# Controller.net
KiCad netlist of a schematic drawn in EAGLE
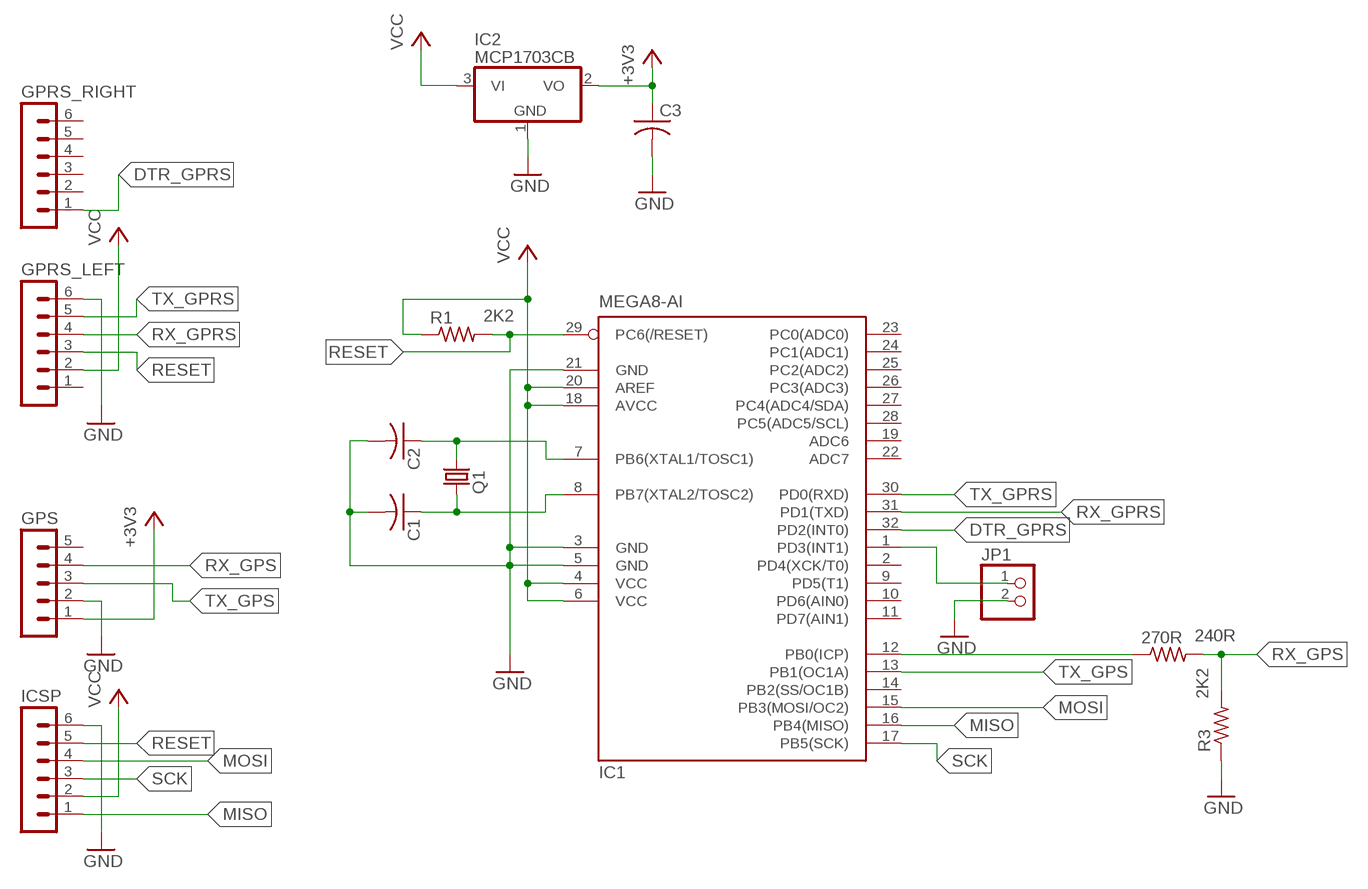
[diagram p0: schematic, sheet 1]

(export (version "E")
  (design (tool "Eeschema 10.0.6"))
  (components
    (comp (ref "270R")
      (value "240R")
      (footprint "eagle-import:M0805")
      (libsource (lib "eagle-import") (part "R-US_M0805"))
    )
    (comp (ref "C1")
      (value "C-US025-024X044")
      (footprint "eagle-import:C025-024X044")
      (libsource (lib "eagle-import") (part "C-US025-024X044"))
    )
    (comp (ref "C2")
      (value "C-US025-024X044")
      (footprint "eagle-import:C025-024X044")
      (libsource (lib "eagle-import") (part "C-US025-024X044"))
    )
    (comp (ref "C3")
      (value "C-US025-024X044")
      (footprint "eagle-import:C025-024X044")
      (libsource (lib "eagle-import") (part "C-US025-024X044"))
    )
    (comp (ref "GPRS_LEFT")
      (value "MA06-1")
      (footprint "eagle-import:MA06-1")
      (libsource (lib "eagle-import") (part "MA06-1"))
    )
    (comp (ref "GPRS_RIGHT")
      (value "MA06-1")
      (footprint "eagle-import:MA06-1")
      (libsource (lib "eagle-import") (part "MA06-1"))
    )
    (comp (ref "GPS")
      (value "MA05-1")
      (footprint "eagle-import:MA05-1")
      (libsource (lib "eagle-import") (part "MA05-1"))
    )
    (comp (ref "IC1")
      (value "MEGA8-AI")
      (footprint "eagle-import:TQFP32-08")
      (fields (field (name "MPN") "ATMEGA8-16AU"))
      (libsource (lib "eagle-import") (part "MEGA8-AI"))
    )
    (comp (ref "IC2")
      (value "MCP1703CB")
      (footprint "eagle-import:SOT23")
      (libsource (lib "eagle-import") (part "MCP1703CB"))
    )
    (comp (ref "ICSP")
      (value "MA06-1")
      (footprint "eagle-import:MA06-1")
      (libsource (lib "eagle-import") (part "MA06-1"))
    )
    (comp (ref "JP1")
      (value "PINHD-1X2")
      (footprint "eagle-import:1X02")
      (libsource (lib "eagle-import") (part "PINHD-1X2"))
    )
    (comp (ref "Q1")
      (value "CRYSTALHC49U-V")
      (footprint "eagle-import:HC49U-V")
      (libsource (lib "eagle-import") (part "CRYSTALHC49U-V"))
    )
    (comp (ref "R1")
      (value "2K2")
      (footprint "eagle-import:M0805")
      (libsource (lib "eagle-import") (part "R-US_M0805"))
    )
    (comp (ref "R3")
      (value "2K2")
      (footprint "eagle-import:M0805")
      (libsource (lib "eagle-import") (part "R-US_M0805"))
    )
  )
  (nets
    (net (code "1") (name "+3V3") (class "Default")
      (node (ref "C3") (pin "1") (pinfunction "1_1") (pintype "passive"))
      (node (ref "GPS") (pin "1") (pinfunction "1_1") (pintype "passive"))
      (node (ref "IC2") (pin "2") (pinfunction "VO_2") (pintype "passive"))
    )
    (net (code "2") (name "DTR_GPRS") (class "Default")
      (node (ref "GPRS_RIGHT") (pin "1") (pinfunction "1_1") (pintype "passive"))
      (node (ref "IC1") (pin "32") (pinfunction "PD2(INT0)_32") (pintype "bidirectional"))
    )
    (net (code "3") (name "GND") (class "Default")
      (node (ref "C1") (pin "2") (pinfunction "2_2") (pintype "passive"))
      (node (ref "C2") (pin "2") (pinfunction "2_2") (pintype "passive"))
      (node (ref "C3") (pin "2") (pinfunction "2_2") (pintype "passive"))
      (node (ref "GPRS_LEFT") (pin "6") (pinfunction "6_6") (pintype "passive"))
      (node (ref "GPS") (pin "2") (pinfunction "2_2") (pintype "passive"))
      (node (ref "IC1") (pin "21") (pinfunction "GND_21") (pintype "power_in"))
      (node (ref "IC1") (pin "3") (pinfunction "GND_3") (pintype "power_in"))
      (node (ref "IC1") (pin "5") (pinfunction "GND_5") (pintype "power_in"))
      (node (ref "IC2") (pin "1") (pinfunction "GND_1") (pintype "passive"))
      (node (ref "ICSP") (pin "6") (pinfunction "6_6") (pintype "passive"))
      (node (ref "JP1") (pin "2") (pinfunction "2_2") (pintype "passive"))
      (node (ref "R3") (pin "1") (pinfunction "1_1") (pintype "passive"))
    )
    (net (code "4") (name "MISO") (class "Default")
      (node (ref "IC1") (pin "16") (pinfunction "PB4(MISO)_16") (pintype "bidirectional"))
      (node (ref "ICSP") (pin "1") (pinfunction "1_1") (pintype "passive"))
    )
    (net (code "5") (name "MOSI") (class "Default")
      (node (ref "IC1") (pin "15") (pinfunction "PB3(MOSI/OC2)_15") (pintype "bidirectional"))
      (node (ref "ICSP") (pin "4") (pinfunction "4_4") (pintype "passive"))
    )
    (net (code "6") (name "Net-(IC1-PB0(ICP))") (class "Default")
      (node (ref "270R") (pin "1") (pinfunction "1_1") (pintype "passive"))
      (node (ref "IC1") (pin "12") (pinfunction "PB0(ICP)_12") (pintype "bidirectional"))
    )
    (net (code "7") (name "Net-(IC1-PB6(XTAL1{slash}TOSC1))") (class "Default")
      (node (ref "C2") (pin "1") (pinfunction "1_1") (pintype "passive"))
      (node (ref "IC1") (pin "7") (pinfunction "PB6(XTAL1/TOSC1)_7") (pintype "bidirectional"))
      (node (ref "Q1") (pin "2") (pinfunction "2_2") (pintype "passive"))
    )
    (net (code "8") (name "Net-(IC1-PB7(XTAL2{slash}TOSC2))") (class "Default")
      (node (ref "C1") (pin "1") (pinfunction "1_1") (pintype "passive"))
      (node (ref "IC1") (pin "8") (pinfunction "PB7(XTAL2/TOSC2)_8") (pintype "bidirectional"))
      (node (ref "Q1") (pin "1") (pinfunction "1_1") (pintype "passive"))
    )
    (net (code "9") (name "Net-(IC1-PD3(INT1))") (class "Default")
      (node (ref "IC1") (pin "1") (pinfunction "PD3(INT1)_1") (pintype "bidirectional"))
      (node (ref "JP1") (pin "1") (pinfunction "1_1") (pintype "passive"))
    )
    (net (code "10") (name "RESET") (class "Default")
      (node (ref "GPRS_LEFT") (pin "3") (pinfunction "3_3") (pintype "passive"))
      (node (ref "IC1") (pin "29") (pinfunction "PC6(/RESET)_29") (pintype "bidirectional"))
      (node (ref "ICSP") (pin "5") (pinfunction "5_5") (pintype "passive"))
      (node (ref "R1") (pin "2") (pinfunction "2_2") (pintype "passive"))
    )
    (net (code "11") (name "RX_GPRS") (class "Default")
      (node (ref "GPRS_LEFT") (pin "4") (pinfunction "4_4") (pintype "passive"))
      (node (ref "IC1") (pin "31") (pinfunction "PD1(TXD)_31") (pintype "bidirectional"))
    )
    (net (code "12") (name "RX_GPS") (class "Default")
      (node (ref "270R") (pin "2") (pinfunction "2_2") (pintype "passive"))
      (node (ref "GPS") (pin "4") (pinfunction "4_4") (pintype "passive"))
      (node (ref "R3") (pin "2") (pinfunction "2_2") (pintype "passive"))
    )
    (net (code "13") (name "SCK") (class "Default")
      (node (ref "IC1") (pin "17") (pinfunction "PB5(SCK)_17") (pintype "bidirectional"))
      (node (ref "ICSP") (pin "3") (pinfunction "3_3") (pintype "passive"))
    )
    (net (code "14") (name "TX_GPRS") (class "Default")
      (node (ref "GPRS_LEFT") (pin "5") (pinfunction "5_5") (pintype "passive"))
      (node (ref "IC1") (pin "30") (pinfunction "PD0(RXD)_30") (pintype "bidirectional"))
    )
    (net (code "15") (name "TX_GPS") (class "Default")
      (node (ref "GPS") (pin "3") (pinfunction "3_3") (pintype "passive"))
      (node (ref "IC1") (pin "13") (pinfunction "PB1(OC1A)_13") (pintype "bidirectional"))
    )
    (net (code "16") (name "VCC") (class "Default")
      (node (ref "GPRS_LEFT") (pin "2") (pinfunction "2_2") (pintype "passive"))
      (node (ref "IC1") (pin "18") (pinfunction "AVCC_18") (pintype "power_in"))
      (node (ref "IC1") (pin "20") (pinfunction "AREF_20") (pintype "passive"))
      (node (ref "IC1") (pin "4") (pinfunction "VCC_4") (pintype "power_in"))
      (node (ref "IC1") (pin "6") (pinfunction "VCC_6") (pintype "power_in"))
      (node (ref "IC2") (pin "3") (pinfunction "VI_3") (pintype "input"))
      (node (ref "ICSP") (pin "2") (pinfunction "2_2") (pintype "passive"))
      (node (ref "R1") (pin "1") (pinfunction "1_1") (pintype "passive"))
    )
    (net (code "17") (name "unconnected-(GPRS_LEFT-Pad1)") (class "Default")
      (node (ref "GPRS_LEFT") (pin "1") (pinfunction "1_1") (pintype "passive"))
    )
    (net (code "18") (name "unconnected-(GPRS_RIGHT-Pad2)") (class "Default")
      (node (ref "GPRS_RIGHT") (pin "2") (pinfunction "2_2") (pintype "passive"))
    )
    (net (code "19") (name "unconnected-(GPRS_RIGHT-Pad3)") (class "Default")
      (node (ref "GPRS_RIGHT") (pin "3") (pinfunction "3_3") (pintype "passive"))
    )
    (net (code "20") (name "unconnected-(GPRS_RIGHT-Pad4)") (class "Default")
      (node (ref "GPRS_RIGHT") (pin "4") (pinfunction "4_4") (pintype "passive"))
    )
    (net (code "21") (name "unconnected-(GPRS_RIGHT-Pad5)") (class "Default")
      (node (ref "GPRS_RIGHT") (pin "5") (pinfunction "5_5") (pintype "passive"))
    )
    (net (code "22") (name "unconnected-(GPRS_RIGHT-Pad6)") (class "Default")
      (node (ref "GPRS_RIGHT") (pin "6") (pinfunction "6_6") (pintype "passive"))
    )
    (net (code "23") (name "unconnected-(GPS-Pad5)") (class "Default")
      (node (ref "GPS") (pin "5") (pinfunction "5_5") (pintype "passive"))
    )
    (net (code "24") (name "unconnected-(IC1-ADC6-Pad19)") (class "Default")
      (node (ref "IC1") (pin "19") (pinfunction "ADC6_19") (pintype "bidirectional"))
    )
    (net (code "25") (name "unconnected-(IC1-ADC7-Pad22)") (class "Default")
      (node (ref "IC1") (pin "22") (pinfunction "ADC7_22") (pintype "bidirectional"))
    )
    (net (code "26") (name "unconnected-(IC1-PB2(SS{slash}OC1B)-Pad14)") (class "Default")
      (node (ref "IC1") (pin "14") (pinfunction "PB2(SS/OC1B)_14") (pintype "bidirectional"))
    )
    (net (code "27") (name "unconnected-(IC1-PC0(ADC0)-Pad23)") (class "Default")
      (node (ref "IC1") (pin "23") (pinfunction "PC0(ADC0)_23") (pintype "bidirectional"))
    )
    (net (code "28") (name "unconnected-(IC1-PC1(ADC1)-Pad24)") (class "Default")
      (node (ref "IC1") (pin "24") (pinfunction "PC1(ADC1)_24") (pintype "bidirectional"))
    )
    (net (code "29") (name "unconnected-(IC1-PC2(ADC2)-Pad25)") (class "Default")
      (node (ref "IC1") (pin "25") (pinfunction "PC2(ADC2)_25") (pintype "bidirectional"))
    )
    (net (code "30") (name "unconnected-(IC1-PC3(ADC3)-Pad26)") (class "Default")
      (node (ref "IC1") (pin "26") (pinfunction "PC3(ADC3)_26") (pintype "bidirectional"))
    )
    (net (code "31") (name "unconnected-(IC1-PC4(ADC4{slash}SDA)-Pad27)") (class "Default")
      (node (ref "IC1") (pin "27") (pinfunction "PC4(ADC4/SDA)_27") (pintype "bidirectional"))
    )
    (net (code "32") (name "unconnected-(IC1-PC5(ADC5{slash}SCL)-Pad28)") (class "Default")
      (node (ref "IC1") (pin "28") (pinfunction "PC5(ADC5/SCL)_28") (pintype "bidirectional"))
    )
    (net (code "33") (name "unconnected-(IC1-PD4(XCK{slash}T0)-Pad2)") (class "Default")
      (node (ref "IC1") (pin "2") (pinfunction "PD4(XCK/T0)_2") (pintype "bidirectional"))
    )
    (net (code "34") (name "unconnected-(IC1-PD5(T1)-Pad9)") (class "Default")
      (node (ref "IC1") (pin "9") (pinfunction "PD5(T1)_9") (pintype "bidirectional"))
    )
    (net (code "35") (name "unconnected-(IC1-PD6(AIN0)-Pad10)") (class "Default")
      (node (ref "IC1") (pin "10") (pinfunction "PD6(AIN0)_10") (pintype "bidirectional"))
    )
    (net (code "36") (name "unconnected-(IC1-PD7(AIN1)-Pad11)") (class "Default")
      (node (ref "IC1") (pin "11") (pinfunction "PD7(AIN1)_11") (pintype "bidirectional"))
    )
  )
)
